# Skematik_Grader-GPS.net
KiCad netlist of a schematic drawn in Altium Designer
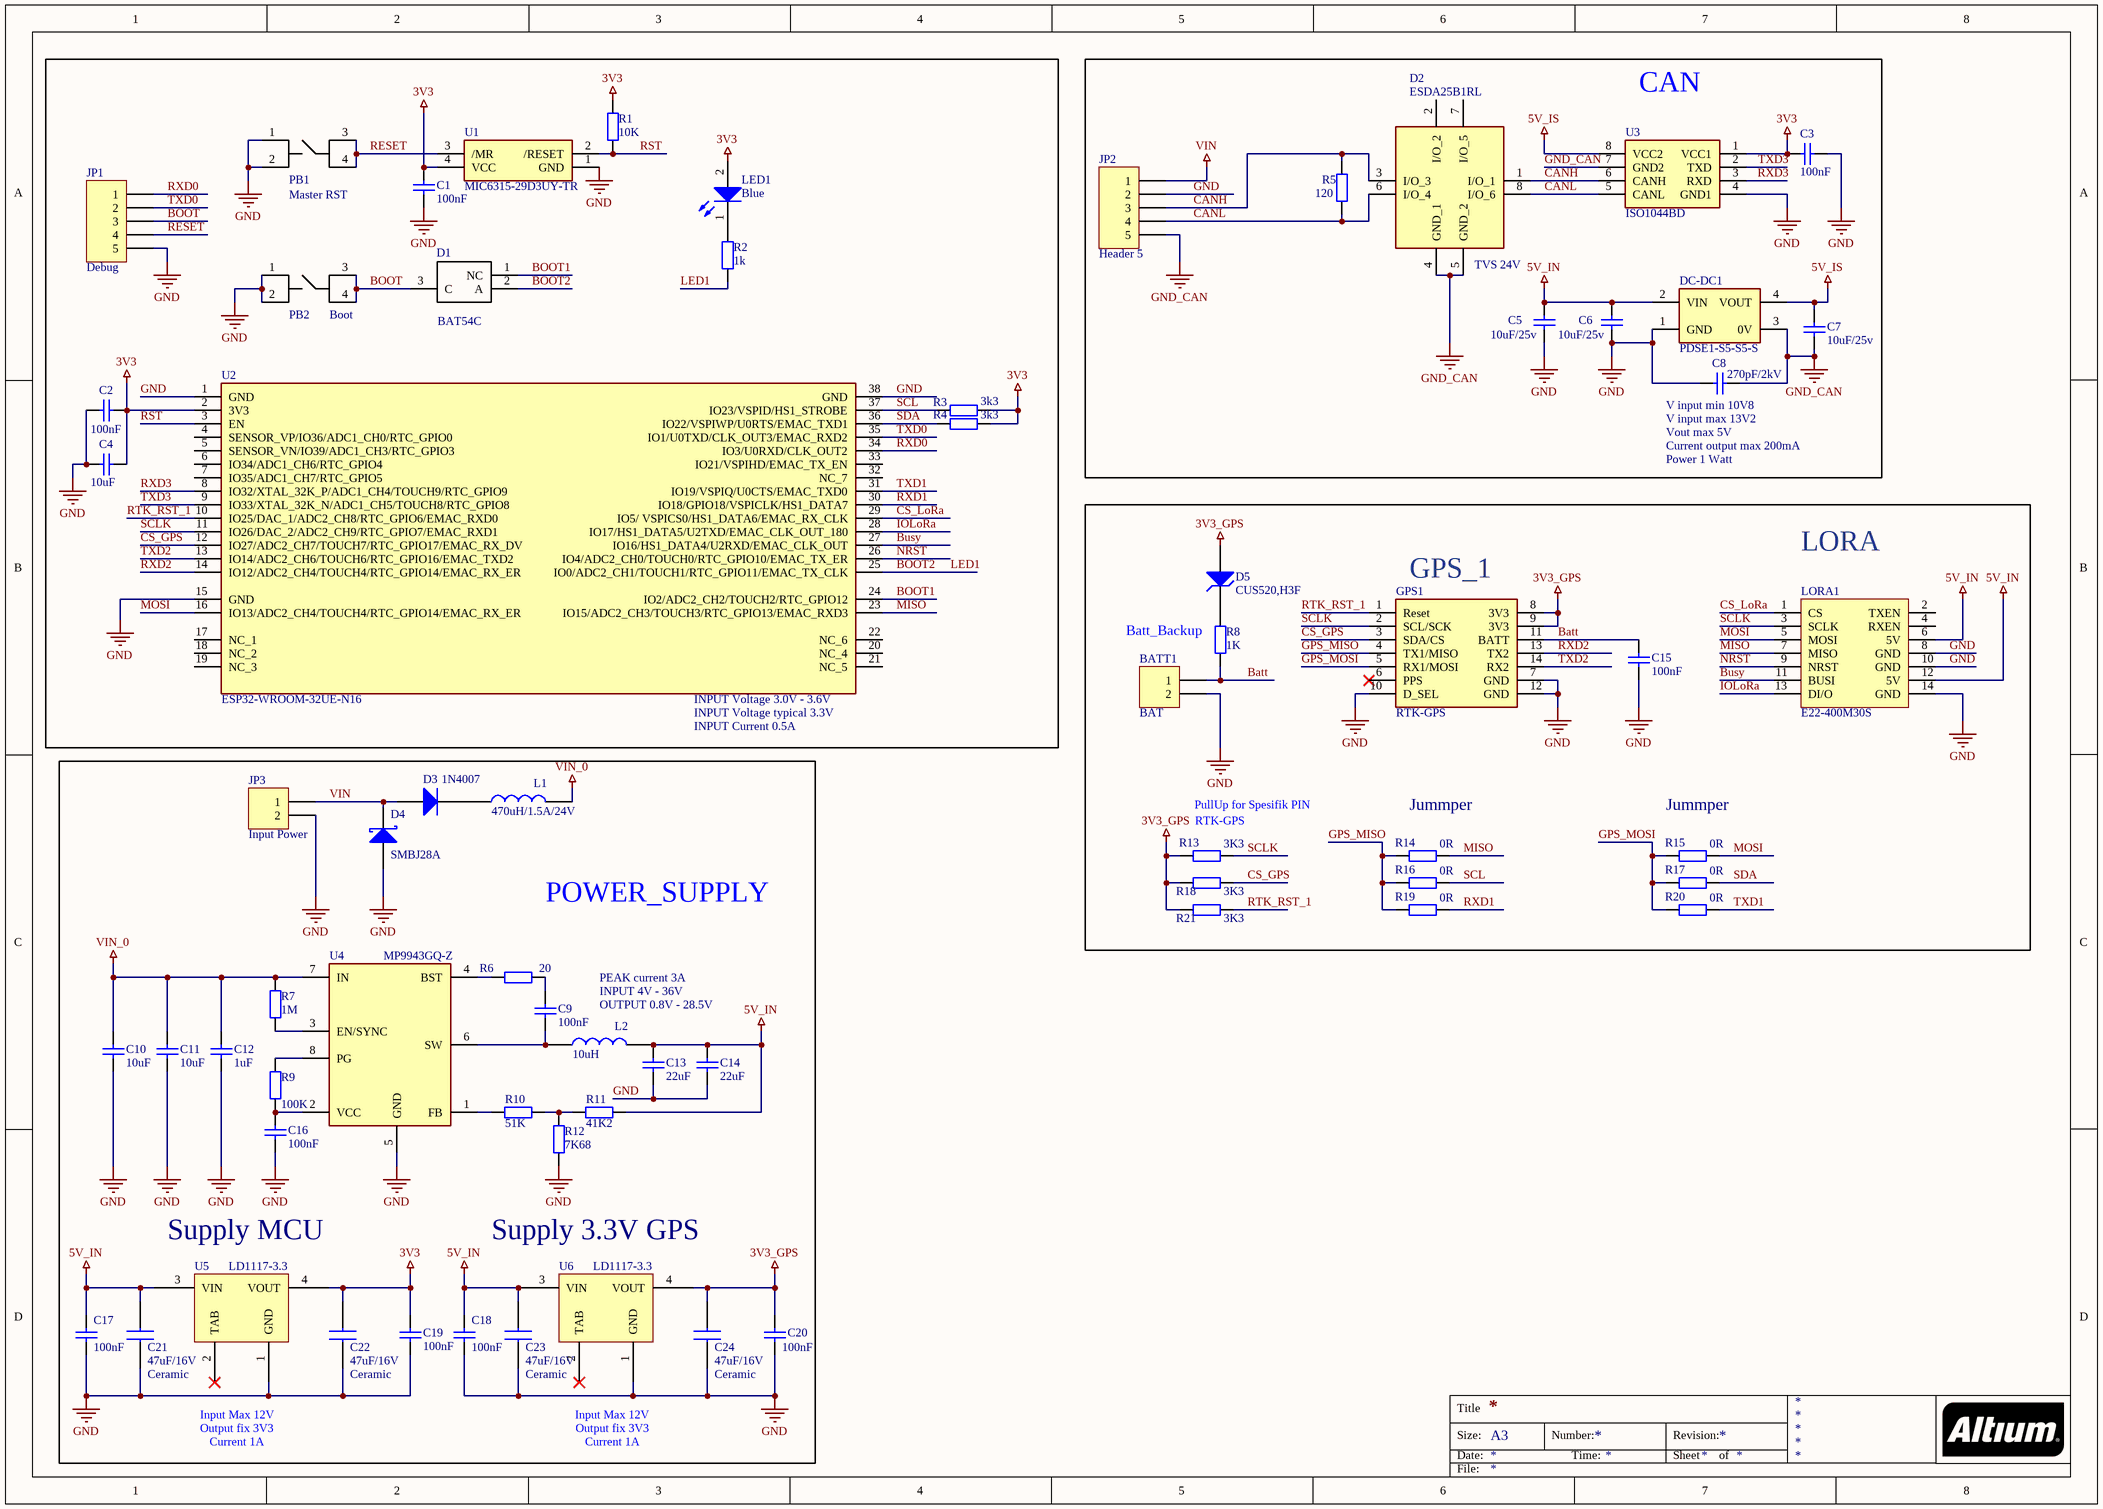
[diagram p0: Skematik_Grader-GPS.SchDoc]

(export (version "E")
  (design (tool "Eeschema 10.0.6"))
  (components
    (comp (ref "BATT1")
      (value "BAT")
      (footprint "CR1220")
      (description "Header, 2-Pin")
      (fields (field (name "PUBLISHER") "Altium Limited"))
      (libsource (lib "Miscellaneous Connectors") (part "MHDR1X2"))
    )
    (comp (ref "C1")
      (value "100nF")
      (footprint "CAPC2012X135N")
      (description "Capacitor")
      (fields (field (name "PUBLISHER") "Altium Limited"))
      (libsource (lib "Miscellaneous Devices") (part "Cap"))
    )
    (comp (ref "C2")
      (value "100nF")
      (footprint "CAPC2012X135N")
      (description "Capacitor")
      (fields (field (name "PUBLISHER") "Altium Limited"))
      (libsource (lib "Miscellaneous Devices") (part "Cap"))
    )
    (comp (ref "C3")
      (value "100nF")
      (footprint "CAPC2012X135N")
      (description "Capacitor")
      (fields (field (name "PUBLISHER") "Altium Limited"))
      (libsource (lib "Miscellaneous Devices") (part "Cap"))
    )
    (comp (ref "C4")
      (value "10uF")
      (footprint "CAPC3216X100N")
      (description "Capacitor")
      (fields (field (name "PUBLISHER") "Altium Limited"))
      (libsource (lib "Miscellaneous Devices") (part "Cap"))
    )
    (comp (ref "C5")
      (value "10uF/25v")
      (footprint "CAPC3216X180N")
      (description "Capacitor")
      (fields (field (name "Comment") "10uF") (field (name "PUBLISHER") "Altium Limited"))
      (libsource (lib "Miscellaneous Devices") (part "Cap"))
    )
    (comp (ref "C6")
      (value "10uF/25v")
      (footprint "CAPC3216X180N")
      (description "Capacitor")
      (fields (field (name "Comment") "10uF") (field (name "PUBLISHER") "Altium Limited"))
      (libsource (lib "Miscellaneous Devices") (part "Cap"))
    )
    (comp (ref "C7")
      (value "10uF/25v")
      (footprint "CAPC3216X100N")
      (description "Capacitor")
      (fields (field (name "Comment") "2.2uF/25V") (field (name "PUBLISHER") "Altium Limited"))
      (libsource (lib "Miscellaneous Devices") (part "Cap"))
    )
    (comp (ref "C8")
      (value "270pF/2kV")
      (footprint "CAPC3216X175N")
      (description "Capacitor")
      (fields (field (name "PUBLISHER") "Altium Limited"))
      (libsource (lib "Miscellaneous Devices") (part "Cap"))
    )
    (comp (ref "C9")
      (value "100nF")
      (footprint "CAPC2012X135N")
      (description "Capacitor")
      (fields (field (name "PUBLISHER") "Altium Limited"))
      (libsource (lib "Miscellaneous Devices") (part "Cap"))
    )
    (comp (ref "C10")
      (value "10uF")
      (footprint "CAPC3216X180N")
      (description "Capacitor")
      (fields (field (name "PUBLISHER") "Altium Limited"))
      (libsource (lib "Miscellaneous Devices") (part "Cap"))
    )
    (comp (ref "C11")
      (value "10uF")
      (footprint "CAPC3216X180N")
      (description "Capacitor")
      (fields (field (name "PUBLISHER") "Altium Limited"))
      (libsource (lib "Miscellaneous Devices") (part "Cap"))
    )
    (comp (ref "C12")
      (value "1uF")
      (footprint "CAPC2012X135N")
      (description "Capacitor")
      (fields (field (name "PUBLISHER") "Altium Limited"))
      (libsource (lib "Miscellaneous Devices") (part "Cap"))
    )
    (comp (ref "C13")
      (value "22uF")
      (footprint "CAPC3216X180N")
      (description "Capacitor")
      (fields (field (name "PUBLISHER") "Altium Limited"))
      (libsource (lib "Miscellaneous Devices") (part "Cap"))
    )
    (comp (ref "C14")
      (value "22uF")
      (footprint "CAPC3216X180N")
      (description "Capacitor")
      (fields (field (name "PUBLISHER") "Altium Limited"))
      (libsource (lib "Miscellaneous Devices") (part "Cap"))
    )
    (comp (ref "C15")
      (value "100nF")
      (footprint "CAPC2012X135N")
      (description "Capacitor")
      (fields (field (name "PUBLISHER") "Altium Limited"))
      (libsource (lib "Miscellaneous Devices") (part "Cap"))
    )
    (comp (ref "C16")
      (value "100nF")
      (footprint "CAPC2012X135N")
      (description "Capacitor")
      (fields (field (name "PUBLISHER") "Altium Limited"))
      (libsource (lib "Miscellaneous Devices") (part "Cap"))
    )
    (comp (ref "C17")
      (value "100nF")
      (footprint "CAPC2012X135N")
      (description "Capacitor")
      (fields (field (name "PUBLISHER") "Altium Limited"))
      (libsource (lib "Miscellaneous Devices") (part "Cap"))
    )
    (comp (ref "C18")
      (value "100nF")
      (footprint "CAPC2012X135N")
      (description "Capacitor")
      (fields (field (name "PUBLISHER") "Altium Limited"))
      (libsource (lib "Miscellaneous Devices") (part "Cap"))
    )
    (comp (ref "C19")
      (value "100nF")
      (footprint "CAPC2012X135N")
      (description "Capacitor")
      (fields (field (name "PUBLISHER") "Altium Limited"))
      (libsource (lib "Miscellaneous Devices") (part "Cap"))
    )
    (comp (ref "C20")
      (value "100nF")
      (footprint "CAPC2012X135N")
      (description "Capacitor")
      (fields (field (name "PUBLISHER") "Altium Limited"))
      (libsource (lib "Miscellaneous Devices") (part "Cap"))
    )
    (comp (ref "C21")
      (value "47uF/16V")
      (footprint "CAPC3225X220N")
      (description "Capacitor")
      (fields
        (field (name "MANUFACTURER_PART_NUMBER") "KCM55WC71E107MH13L")
        (field (name "MOUSER PART NUMBER") "81-KCM55WC71E107MH13")
        (field (name "TYPE") "Ceramic")
      )
      (libsource (lib "*") (part "KCM55WC71E107MH13L"))
    )
    (comp (ref "C22")
      (value "47uF/16V")
      (footprint "CAPC3225X220N")
      (description "Capacitor")
      (fields
        (field (name "MANUFACTURER_PART_NUMBER") "KCM55WC71E107MH13L")
        (field (name "MOUSER PART NUMBER") "81-KCM55WC71E107MH13")
        (field (name "TYPE") "Ceramic")
      )
      (libsource (lib "*") (part "KCM55WC71E107MH13L"))
    )
    (comp (ref "C23")
      (value "47uF/16V")
      (footprint "CAPC3225X220N")
      (description "Capacitor")
      (fields
        (field (name "MANUFACTURER_PART_NUMBER") "KCM55WC71E107MH13L")
        (field (name "MOUSER PART NUMBER") "81-KCM55WC71E107MH13")
        (field (name "TYPE") "Ceramic")
      )
      (libsource (lib "*") (part "KCM55WC71E107MH13L"))
    )
    (comp (ref "C24")
      (value "47uF/16V")
      (footprint "CAPC3225X220N")
      (description "Capacitor")
      (fields
        (field (name "MANUFACTURER_PART_NUMBER") "KCM55WC71E107MH13L")
        (field (name "MOUSER PART NUMBER") "81-KCM55WC71E107MH13")
        (field (name "TYPE") "Ceramic")
      )
      (libsource (lib "*") (part "KCM55WC71E107MH13L"))
    )
    (comp (ref "D1") (value "BAT54C") (footprint "SC59-3") (libsource (lib "Sigit") (part "RB420")))
    (comp (ref "D2")
      (value "ESDA25B1RL")
      (footprint "SOIC127P600X175-8AN")
      (description "TVS DIODA")
      (fields (field (name "MOUSER PART NUMBER") "511-ESDA25B1-TR"))
      (libsource (lib "bayu") (part "ESDA25B1RL"))
    )
    (comp (ref "D3")
      (value "1N4007")
      (footprint "DO-214AC")
      (description "1 Amp General Purpose Rectifier")
      (fields (field (name "PUBLISHER") "Altium Limited"))
      (libsource (lib "Miscellaneous Devices") (part "Diode 1N4001"))
    )
    (comp (ref "D4")
      (value "SMBJ28A")
      (footprint "PBL - SMD Packages:DO-214AA")
      (description "Schottky Diode")
      (fields (field (name "PUBLISHER") "Altium Limited"))
      (libsource (lib "Miscellaneous Devices") (part "D Schottky"))
    )
    (comp (ref "D5")
      (value "CUS520,H3F")
      (footprint "SOD323")
      (description "Zener Diode")
      (fields (field (name "PUBLISHER") "Altium Limited"))
      (libsource (lib "Miscellaneous Devices") (part "D Zener"))
    )
    (comp (ref "DC-DC1")
      (value "PDSE1-S5-S5-S")
      (footprint "PDSE1-S (1W)")
      (description "DC-DC 24 to 12 \r\nPDSE1-S24-S12-S")
      (libsource (lib "rapp") (part "PDSE1-S24-S12-S"))
    )
    (comp (ref "GPS1")
      (value "RTK-GPS")
      (footprint "ZED-F9P")
      (description "GPS Sensor")
      (libsource (lib "rapp") (part "ZED-F9P"))
    )
    (comp (ref "JP1")
      (value "Debug")
      (footprint "HDR1X5")
      (description "Header, 5-Pin")
      (fields (field (name "PUBLISHER") "Altium Limited"))
      (libsource (lib "Miscellaneous Connectors") (part "Header 5"))
    )
    (comp (ref "JP2")
      (value "Header 5")
      (footprint "Term_Block - 5P")
      (description "Header, 5-Pin")
      (fields (field (name "PUBLISHER") "Altium Limited"))
      (libsource (lib "Miscellaneous Connectors") (part "Header 5"))
    )
    (comp (ref "JP3")
      (value "Input Power")
      (footprint "2828362")
      (description "Header, 2-Pin")
      (fields (field (name "PUBLISHER") "Altium Limited"))
      (libsource (lib "Miscellaneous Connectors") (part "Header 2"))
    )
    (comp (ref "L1")
      (value "470uH/1.5A/24V")
      (footprint "INDP9630X28N")
      (description "Inductor")
      (fields
        (field (name "MANUFACTURER_PART_NUMBER") "MPL-AL5050-100")
        (field (name "MOUSER PART NUMBER") "946-MPL-AL5050-100")
      )
      (libsource (lib "*") (part "MPL-AL5050-100"))
    )
    (comp (ref "L2")
      (value "10uH")
      (footprint "IND_5.4x5.3")
      (description "Inductor")
      (fields
        (field (name "MANUFACTURER_PART_NUMBER") "MPL-AL5050-100")
        (field (name "MOUSER PART NUMBER") "946-MPL-AL5050-100")
      )
      (libsource (lib "*") (part "MPL-AL5050-100"))
    )
    (comp (ref "LED1")
      (value "Blue")
      (footprint "LED-0805-A")
      (description "Typical Blue GaAs LED")
      (fields (field (name "PUBLISHER") "Altium Limited"))
      (libsource (lib "Miscellaneous Devices") (part "LED1"))
    )
    (comp (ref "LORA1")
      (value "E22-400M30S")
      (footprint "22s-V3")
      (description "Lora 22S / Lora 30S")
      (libsource (lib "rapp") (part "Lora"))
    )
    (comp (ref "PB1")
      (value "Master RST")
      (footprint "PushButton1688")
      (libsource (lib "Sigit") (part "PB_SW_1"))
    )
    (comp (ref "PB2") (value "Boot") (footprint "PushButton1688") (libsource (lib "Sigit") (part "PB_SW_1")))
    (comp (ref "R1")
      (value "10K")
      (footprint "RESC2012X70N")
      (description "Resistor")
      (fields (field (name "PUBLISHER") "Altium Limited"))
      (libsource (lib "Miscellaneous Devices") (part "Res2"))
    )
    (comp (ref "R2")
      (value "1k")
      (footprint "RESC2012X70N")
      (description "Resistor")
      (fields (field (name "PUBLISHER") "Altium Limited"))
      (libsource (lib "Miscellaneous Devices") (part "Res2"))
    )
    (comp (ref "R3")
      (value "3k3")
      (footprint "RESC2012X70N")
      (description "Resistor")
      (fields (field (name "PUBLISHER") "Altium Limited"))
      (libsource (lib "Miscellaneous Devices") (part "Res2"))
    )
    (comp (ref "R4")
      (value "3k3")
      (footprint "RESC2012X70N")
      (description "Resistor")
      (fields (field (name "PUBLISHER") "Altium Limited"))
      (libsource (lib "Miscellaneous Devices") (part "Res2"))
    )
    (comp (ref "R5")
      (value "120")
      (footprint "RESC2012X70N")
      (description "Resistor")
      (fields (field (name "PUBLISHER") "Altium Limited"))
      (libsource (lib "") (part "Res2_3"))
    )
    (comp (ref "R6")
      (value "20")
      (footprint "RESC2012X70N")
      (description "Resistor")
      (fields (field (name "PUBLISHER") "Altium Limited"))
      (libsource (lib "") (part "Res2_3"))
    )
    (comp (ref "R7")
      (value "1M")
      (footprint "RESC2012X70N")
      (description "Resistor")
      (fields (field (name "PUBLISHER") "Altium Limited"))
      (libsource (lib "") (part "Res2_1"))
    )
    (comp (ref "R8")
      (value "1K")
      (footprint "RESC2012X70N")
      (description "Resistor")
      (fields (field (name "PUBLISHER") "Altium Limited"))
      (libsource (lib "") (part "Res2_2"))
    )
    (comp (ref "R9")
      (value "100K")
      (footprint "RESC2012X70N")
      (description "Resistor")
      (fields (field (name "PUBLISHER") "Altium Limited"))
      (libsource (lib "") (part "Res2_1"))
    )
    (comp (ref "R10")
      (value "51K")
      (footprint "RESC2012X70N")
      (description "Resistor")
      (fields (field (name "PUBLISHER") "Altium Limited"))
      (libsource (lib "") (part "Res2_3"))
    )
    (comp (ref "R11")
      (value "41K2")
      (footprint "RESC2012X70N")
      (description "Resistor")
      (fields (field (name "PUBLISHER") "Altium Limited"))
      (libsource (lib "") (part "Res2_3"))
    )
    (comp (ref "R12")
      (value "7K68")
      (footprint "RESC2012X70N")
      (description "Resistor")
      (fields (field (name "PUBLISHER") "Altium Limited"))
      (libsource (lib "Miscellaneous Devices") (part "Res2"))
    )
    (comp (ref "R13")
      (value "3K3")
      (footprint "RESC2012X70N")
      (description "Resistor")
      (fields (field (name "PUBLISHER") "Altium Limited"))
      (libsource (lib "") (part "Res2_1"))
    )
    (comp (ref "R14")
      (value "0R")
      (footprint "RESC2012X70N")
      (description "Resistor")
      (fields (field (name "PUBLISHER") "Altium Limited"))
      (libsource (lib "") (part "Res2_1"))
    )
    (comp (ref "R15")
      (value "0R")
      (footprint "RESC2012X70N")
      (description "Resistor")
      (fields (field (name "PUBLISHER") "Altium Limited"))
      (libsource (lib "") (part "Res2_1"))
    )
    (comp (ref "R16")
      (value "0R")
      (footprint "RESC2012X70N")
      (description "Resistor")
      (fields (field (name "PUBLISHER") "Altium Limited"))
      (libsource (lib "") (part "Res2_1"))
    )
    (comp (ref "R17")
      (value "0R")
      (footprint "RESC2012X70N")
      (description "Resistor")
      (fields (field (name "PUBLISHER") "Altium Limited"))
      (libsource (lib "") (part "Res2_1"))
    )
    (comp (ref "R18")
      (value "3K3")
      (footprint "RESC2012X70N")
      (description "Resistor")
      (fields (field (name "PUBLISHER") "Altium Limited"))
      (libsource (lib "Miscellaneous Devices") (part "Res2"))
    )
    (comp (ref "R19")
      (value "0R")
      (footprint "RESC2012X70N")
      (description "Resistor")
      (fields (field (name "PUBLISHER") "Altium Limited"))
      (libsource (lib "") (part "Res2_1"))
    )
    (comp (ref "R20")
      (value "0R")
      (footprint "RESC2012X70N")
      (description "Resistor")
      (fields (field (name "PUBLISHER") "Altium Limited"))
      (libsource (lib "") (part "Res2_1"))
    )
    (comp (ref "R21")
      (value "3K3")
      (footprint "RESC2012X70N")
      (description "Resistor")
      (fields (field (name "PUBLISHER") "Altium Limited"))
      (libsource (lib "Miscellaneous Devices") (part "Res2"))
    )
    (comp (ref "U1")
      (value "MIC6315-29D3UY-TR")
      (footprint "MIC631529D3UYTR")
      (description "Integrated Circuit")
      (fields (field (name "MOUSER PART NUMBER") "998-MIC6315-29D3UYTR"))
      (libsource (lib "*") (part "MIC6315-29D3UY-TR"))
    )
    (comp (ref "U2")
      (value "ESP32-WROOM-32UE-N16")
      (footprint "ESP32WROOM32UEN16")
      (libsource (lib "rapp") (part "ESP32-WROOM-32UE-N16A"))
    )
    (comp (ref "U3")
      (value "ISO1044BD")
      (footprint "SOIC127P600X175-8AN")
      (description "Integrated Circuit")
      (fields (field (name "MOUSER PART NUMBER") "595-ISO1044BD"))
      (libsource (lib "*") (part "ISO1044BD"))
    )
    (comp (ref "U4")
      (value "MP9943GQ-Z")
      (footprint "MP9943GQz-smd")
      (description "Integrated Circuit")
      (fields (field (name "MOUSER PART NUMBER") "946-MP9943GQ-Z"))
      (libsource (lib "bayu") (part "MP9943GQ-Z"))
    )
    (comp (ref "U5")
      (value "LD1117-3.3")
      (footprint "PBL - SMD Packages:TO-252")
      (description "AP2114D-3.3TRG1, 3.3V LDO Voltage Regulator")
      (libsource (lib "Sigit") (part "LM1117-3.3V"))
    )
    (comp (ref "U6")
      (value "LD1117-3.3")
      (footprint "PBL - SMD Packages:TO-252")
      (description "AP2114D-3.3TRG1, 3.3V LDO Voltage Regulator")
      (libsource (lib "Sigit") (part "LM1117-3.3V"))
    )
  )
  (nets
    (net (code "1") (name "/BOOT") (class "Default")
      (node (ref "D1") (pin "3") (pinfunction "C_3") (pintype "passive"))
      (node (ref "JP1") (pin "3") (pinfunction "3_3") (pintype "passive"))
      (node (ref "PB2") (pin "3") (pinfunction "3_3") (pintype "passive"))
      (node (ref "PB2") (pin "4") (pinfunction "4_4") (pintype "passive"))
    )
    (net (code "2") (name "/BOOT1") (class "Default")
      (node (ref "D1") (pin "1") (pinfunction "NC_1") (pintype "passive"))
      (node (ref "U2") (pin "24") (pinfunction "IO2/ADC2_CH2/TOUCH2/RTC_GPIO12_24") (pintype "passive"))
    )
    (net (code "3") (name "/BOOT2") (class "Default")
      (node (ref "D1") (pin "2") (pinfunction "A_2") (pintype "passive"))
      (node (ref "R2") (pin "2") (pinfunction "2_2") (pintype "passive"))
      (node (ref "U2") (pin "25") (pinfunction "IO0/ADC2_CH1/TOUCH1/RTC_GPIO11/EMAC_TX_CLK_25") (pintype "passive"))
    )
    (net (code "4") (name "/Batt") (class "Default")
      (node (ref "BATT1") (pin "1") (pinfunction "1_1") (pintype "passive"))
      (node (ref "C15") (pin "2") (pinfunction "2_2") (pintype "passive"))
      (node (ref "GPS1") (pin "11") (pinfunction "BATT_11") (pintype "passive"))
      (node (ref "R8") (pin "1") (pinfunction "1_1") (pintype "passive"))
    )
    (net (code "5") (name "/Busy") (class "Default")
      (node (ref "LORA1") (pin "11") (pinfunction "BUSI_11") (pintype "passive"))
      (node (ref "U2") (pin "27") (pinfunction "IO16/HS1_DATA4/U2RXD/EMAC_CLK_OUT_27") (pintype "passive"))
    )
    (net (code "6") (name "/CANH") (class "Default")
      (node (ref "D2") (pin "1") (pinfunction "I/O_1_1") (pintype "passive"))
      (node (ref "D2") (pin "3") (pinfunction "I/O_3_3") (pintype "passive"))
      (node (ref "JP2") (pin "3") (pinfunction "3_3") (pintype "passive"))
      (node (ref "R5") (pin "1") (pinfunction "1_1") (pintype "passive"))
      (node (ref "U3") (pin "6") (pinfunction "CANH_6") (pintype "passive"))
    )
    (net (code "7") (name "/CANL") (class "Default")
      (node (ref "D2") (pin "6") (pinfunction "I/O_4_6") (pintype "passive"))
      (node (ref "D2") (pin "8") (pinfunction "I/O_6_8") (pintype "passive"))
      (node (ref "JP2") (pin "4") (pinfunction "4_4") (pintype "passive"))
      (node (ref "R5") (pin "2") (pinfunction "2_2") (pintype "passive"))
      (node (ref "U3") (pin "5") (pinfunction "CANL_5") (pintype "passive"))
    )
    (net (code "8") (name "/CS_GPS") (class "Default")
      (node (ref "GPS1") (pin "3") (pinfunction "SDA/CS_3") (pintype "passive"))
      (node (ref "R18") (pin "1") (pinfunction "1_1") (pintype "passive"))
      (node (ref "U2") (pin "12") (pinfunction "IO27/ADC2_CH7/TOUCH7/RTC_GPIO17/EMAC_RX_DV_12") (pintype "passive"))
    )
    (net (code "9") (name "/CS_LoRa") (class "Default")
      (node (ref "LORA1") (pin "1") (pinfunction "CS_1") (pintype "passive"))
      (node (ref "U2") (pin "29") (pinfunction "IO5/_VSPICS0/HS1_DATA6/EMAC_RX_CLK_29") (pintype "passive"))
    )
    (net (code "10") (name "/GPS_MISO") (class "Default")
      (node (ref "GPS1") (pin "4") (pinfunction "TX1/MISO_4") (pintype "passive"))
      (node (ref "R14") (pin "1") (pinfunction "1_1") (pintype "passive"))
      (node (ref "R16") (pin "1") (pinfunction "1_1") (pintype "passive"))
      (node (ref "R19") (pin "1") (pinfunction "1_1") (pintype "passive"))
    )
    (net (code "11") (name "/GPS_MOSI") (class "Default")
      (node (ref "GPS1") (pin "5") (pinfunction "RX1/MOSI_5") (pintype "passive"))
      (node (ref "R15") (pin "1") (pinfunction "1_1") (pintype "passive"))
      (node (ref "R17") (pin "1") (pinfunction "1_1") (pintype "passive"))
      (node (ref "R20") (pin "1") (pinfunction "1_1") (pintype "passive"))
    )
    (net (code "12") (name "/IOLoRa") (class "Default")
      (node (ref "LORA1") (pin "13") (pinfunction "DI/O_13") (pintype "passive"))
      (node (ref "U2") (pin "28") (pinfunction "IO17/HS1_DATA5/U2TXD/EMAC_CLK_OUT_180_28") (pintype "passive"))
    )
    (net (code "13") (name "/MISO") (class "Default")
      (node (ref "LORA1") (pin "7") (pinfunction "MISO_7") (pintype "passive"))
      (node (ref "R14") (pin "2") (pinfunction "2_2") (pintype "passive"))
      (node (ref "U2") (pin "23") (pinfunction "IO15/ADC2_CH3/TOUCH3/RTC_GPIO13/EMAC_RXD3_23") (pintype "passive"))
    )
    (net (code "14") (name "/MOSI") (class "Default")
      (node (ref "LORA1") (pin "5") (pinfunction "MOSI_5") (pintype "passive"))
      (node (ref "R15") (pin "2") (pinfunction "2_2") (pintype "passive"))
      (node (ref "U2") (pin "16") (pinfunction "IO13/ADC2_CH4/TOUCH4/RTC_GPIO14/EMAC_RX_ER_16") (pintype "passive"))
    )
    (net (code "15") (name "/NRST") (class "Default")
      (node (ref "LORA1") (pin "9") (pinfunction "NRST_9") (pintype "passive"))
      (node (ref "U2") (pin "26") (pinfunction "IO4/ADC2_CH0/TOUCH0/RTC_GPIO10/EMAC_TX_ER_26") (pintype "passive"))
    )
    (net (code "16") (name "/RESET") (class "Default")
      (node (ref "JP1") (pin "4") (pinfunction "4_4") (pintype "passive"))
      (node (ref "PB1") (pin "3") (pinfunction "3_3") (pintype "passive"))
      (node (ref "PB1") (pin "4") (pinfunction "4_4") (pintype "passive"))
      (node (ref "U1") (pin "3") (pinfunction "/MR_3") (pintype "passive"))
    )
    (net (code "17") (name "/RST") (class "Default")
      (node (ref "R1") (pin "2") (pinfunction "2_2") (pintype "passive"))
      (node (ref "U1") (pin "2") (pinfunction "/RESET_2") (pintype "passive"))
      (node (ref "U2") (pin "3") (pinfunction "EN_3") (pintype "passive"))
    )
    (net (code "18") (name "/RTK_RST_1") (class "Default")
      (node (ref "GPS1") (pin "1") (pinfunction "Reset_1") (pintype "passive"))
      (node (ref "R21") (pin "1") (pinfunction "1_1") (pintype "passive"))
      (node (ref "U2") (pin "10") (pinfunction "IO25/DAC_1/ADC2_CH8/RTC_GPIO6/EMAC_RXD0_10") (pintype "passive"))
    )
    (net (code "19") (name "/RXD0") (class "Default")
      (node (ref "JP1") (pin "1") (pinfunction "1_1") (pintype "passive"))
      (node (ref "U2") (pin "34") (pinfunction "IO3/U0RXD/CLK_OUT2_34") (pintype "passive"))
    )
    (net (code "20") (name "/RXD1") (class "Default")
      (node (ref "R19") (pin "2") (pinfunction "2_2") (pintype "passive"))
      (node (ref "U2") (pin "30") (pinfunction "IO18/GPIO18/VSPICLK/HS1_DATA7_30") (pintype "passive"))
    )
    (net (code "21") (name "/RXD2") (class "Default")
      (node (ref "GPS1") (pin "13") (pinfunction "TX2_13") (pintype "passive"))
      (node (ref "U2") (pin "14") (pinfunction "IO12/ADC2_CH4/TOUCH4/RTC_GPIO14/EMAC_RX_ER_14") (pintype "passive"))
    )
    (net (code "22") (name "/RXD3") (class "Default")
      (node (ref "U2") (pin "8") (pinfunction "IO32/XTAL_32K_P/ADC1_CH4/TOUCH9/RTC_GPIO9_8") (pintype "passive"))
      (node (ref "U3") (pin "3") (pinfunction "RXD_3") (pintype "passive"))
    )
    (net (code "23") (name "/SCL") (class "Default")
      (node (ref "R16") (pin "2") (pinfunction "2_2") (pintype "passive"))
      (node (ref "R3") (pin "2") (pinfunction "2_2") (pintype "passive"))
      (node (ref "U2") (pin "37") (pinfunction "IO23/VSPID/HS1_STROBE_37") (pintype "passive"))
    )
    (net (code "24") (name "/SCLK") (class "Default")
      (node (ref "GPS1") (pin "2") (pinfunction "SCL/SCK_2") (pintype "passive"))
      (node (ref "LORA1") (pin "3") (pinfunction "SCLK_3") (pintype "passive"))
      (node (ref "R13") (pin "2") (pinfunction "2_2") (pintype "passive"))
      (node (ref "U2") (pin "11") (pinfunction "IO26/DAC_2/ADC2_CH9/RTC_GPIO7/EMAC_RXD1_11") (pintype "passive"))
    )
    (net (code "25") (name "/SDA") (class "Default")
      (node (ref "R17") (pin "2") (pinfunction "2_2") (pintype "passive"))
      (node (ref "R4") (pin "2") (pinfunction "2_2") (pintype "passive"))
      (node (ref "U2") (pin "36") (pinfunction "IO22/VSPIWP/U0RTS/EMAC_TXD1_36") (pintype "passive"))
    )
    (net (code "26") (name "/TXD0") (class "Default")
      (node (ref "JP1") (pin "2") (pinfunction "2_2") (pintype "passive"))
      (node (ref "U2") (pin "35") (pinfunction "IO1/U0TXD/CLK_OUT3/EMAC_RXD2_35") (pintype "passive"))
    )
    (net (code "27") (name "/TXD1") (class "Default")
      (node (ref "R20") (pin "2") (pinfunction "2_2") (pintype "passive"))
      (node (ref "U2") (pin "31") (pinfunction "IO19/VSPIQ/U0CTS/EMAC_TXD0_31") (pintype "passive"))
    )
    (net (code "28") (name "/TXD2") (class "Default")
      (node (ref "GPS1") (pin "14") (pinfunction "RX2_14") (pintype "passive"))
      (node (ref "U2") (pin "13") (pinfunction "IO14/ADC2_CH6/TOUCH6/RTC_GPIO16/EMAC_TXD2_13") (pintype "passive"))
    )
    (net (code "29") (name "/TXD3") (class "Default")
      (node (ref "U2") (pin "9") (pinfunction "IO33/XTAL_32K_N/ADC1_CH5/TOUCH8/RTC_GPIO8_9") (pintype "passive"))
      (node (ref "U3") (pin "2") (pinfunction "TXD_2") (pintype "passive"))
    )
    (net (code "30") (name "3V3") (class "Default")
      (node (ref "C1") (pin "1") (pinfunction "1_1") (pintype "passive"))
      (node (ref "C19") (pin "2") (pinfunction "2_2") (pintype "passive"))
      (node (ref "C2") (pin "2") (pinfunction "2_2") (pintype "passive"))
      (node (ref "C22") (pin "1") (pinfunction "1_1") (pintype "passive"))
      (node (ref "C3") (pin "1") (pinfunction "1_1") (pintype "passive"))
      (node (ref "C4") (pin "2") (pinfunction "2_2") (pintype "passive"))
      (node (ref "LED1") (pin "2") (pinfunction "A_2") (pintype "passive"))
      (node (ref "R1") (pin "1") (pinfunction "1_1") (pintype "passive"))
      (node (ref "R3") (pin "1") (pinfunction "1_1") (pintype "passive"))
      (node (ref "R4") (pin "1") (pinfunction "1_1") (pintype "passive"))
      (node (ref "U1") (pin "4") (pinfunction "VCC_4") (pintype "passive"))
      (node (ref "U2") (pin "2") (pinfunction "3V3_2") (pintype "passive"))
      (node (ref "U3") (pin "1") (pinfunction "VCC1_1") (pintype "passive"))
      (node (ref "U5") (pin "4") (pinfunction "VOUT_4") (pintype "passive"))
    )
    (net (code "31") (name "3V3_GPS") (class "Default")
      (node (ref "C20") (pin "2") (pinfunction "2_2") (pintype "passive"))
      (node (ref "C24") (pin "1") (pinfunction "1_1") (pintype "passive"))
      (node (ref "D5") (pin "1") (pinfunction "A_1") (pintype "passive"))
      (node (ref "GPS1") (pin "8") (pinfunction "3V3_8") (pintype "passive"))
      (node (ref "GPS1") (pin "9") (pinfunction "3V3_9") (pintype "passive"))
      (node (ref "R13") (pin "1") (pinfunction "1_1") (pintype "passive"))
      (node (ref "R18") (pin "2") (pinfunction "2_2") (pintype "passive"))
      (node (ref "R21") (pin "2") (pinfunction "2_2") (pintype "passive"))
      (node (ref "U6") (pin "4") (pinfunction "VOUT_4") (pintype "passive"))
    )
    (net (code "32") (name "5V_IN") (class "Default")
      (node (ref "C13") (pin "2") (pinfunction "2_2") (pintype "passive"))
      (node (ref "C14") (pin "2") (pinfunction "2_2") (pintype "passive"))
      (node (ref "C17") (pin "2") (pinfunction "2_2") (pintype "passive"))
      (node (ref "C18") (pin "2") (pinfunction "2_2") (pintype "passive"))
      (node (ref "C21") (pin "1") (pinfunction "1_1") (pintype "passive"))
      (node (ref "C23") (pin "1") (pinfunction "1_1") (pintype "passive"))
      (node (ref "C5") (pin "2") (pinfunction "2_2") (pintype "passive"))
      (node (ref "C6") (pin "2") (pinfunction "2_2") (pintype "passive"))
      (node (ref "DC-DC1") (pin "2") (pinfunction "VIN_2") (pintype "passive"))
      (node (ref "L2") (pin "2") (pinfunction "2_2") (pintype "passive"))
      (node (ref "LORA1") (pin "12") (pinfunction "5V_12") (pintype "passive"))
      (node (ref "LORA1") (pin "6") (pinfunction "5V_6") (pintype "passive"))
      (node (ref "R11") (pin "1") (pinfunction "1_1") (pintype "passive"))
      (node (ref "U5") (pin "3") (pinfunction "VIN_3") (pintype "passive"))
      (node (ref "U6") (pin "3") (pinfunction "VIN_3") (pintype "passive"))
    )
    (net (code "33") (name "5V_IS") (class "Default")
      (node (ref "C7") (pin "1") (pinfunction "1_1") (pintype "passive"))
      (node (ref "DC-DC1") (pin "4") (pinfunction "VOUT_4") (pintype "passive"))
      (node (ref "U3") (pin "8") (pinfunction "VCC2_8") (pintype "passive"))
    )
    (net (code "34") (name "GND") (class "Default")
      (node (ref "BATT1") (pin "2") (pinfunction "2_2") (pintype "passive"))
      (node (ref "C1") (pin "2") (pinfunction "2_2") (pintype "passive"))
      (node (ref "C10") (pin "1") (pinfunction "1_1") (pintype "passive"))
      (node (ref "C11") (pin "1") (pinfunction "1_1") (pintype "passive"))
      (node (ref "C12") (pin "1") (pinfunction "1_1") (pintype "passive"))
      (node (ref "C13") (pin "1") (pinfunction "1_1") (pintype "passive"))
      (node (ref "C14") (pin "1") (pinfunction "1_1") (pintype "passive"))
      (node (ref "C15") (pin "1") (pinfunction "1_1") (pintype "passive"))
      (node (ref "C16") (pin "1") (pinfunction "1_1") (pintype "passive"))
      (node (ref "C17") (pin "1") (pinfunction "1_1") (pintype "passive"))
      (node (ref "C18") (pin "1") (pinfunction "1_1") (pintype "passive"))
      (node (ref "C19") (pin "1") (pinfunction "1_1") (pintype "passive"))
      (node (ref "C2") (pin "1") (pinfunction "1_1") (pintype "passive"))
      (node (ref "C20") (pin "1") (pinfunction "1_1") (pintype "passive"))
      (node (ref "C21") (pin "2") (pinfunction "2_2") (pintype "passive"))
      (node (ref "C22") (pin "2") (pinfunction "2_2") (pintype "passive"))
      (node (ref "C23") (pin "2") (pinfunction "2_2") (pintype "passive"))
      (node (ref "C24") (pin "2") (pinfunction "2_2") (pintype "passive"))
      (node (ref "C3") (pin "2") (pinfunction "2_2") (pintype "passive"))
      (node (ref "C4") (pin "1") (pinfunction "1_1") (pintype "passive"))
      (node (ref "C5") (pin "1") (pinfunction "1_1") (pintype "passive"))
      (node (ref "C6") (pin "1") (pinfunction "1_1") (pintype "passive"))
      (node (ref "C8") (pin "1") (pinfunction "1_1") (pintype "passive"))
      (node (ref "D4") (pin "1") (pinfunction "A_1") (pintype "passive"))
      (node (ref "DC-DC1") (pin "1") (pinfunction "GND_1") (pintype "passive"))
      (node (ref "GPS1") (pin "10") (pinfunction "D_SEL_10") (pintype "passive"))
      (node (ref "GPS1") (pin "12") (pinfunction "GND_12") (pintype "passive"))
      (node (ref "GPS1") (pin "7") (pinfunction "GND_7") (pintype "passive"))
      (node (ref "JP1") (pin "5") (pinfunction "5_5") (pintype "passive"))
      (node (ref "JP2") (pin "2") (pinfunction "2_2") (pintype "passive"))
      (node (ref "JP3") (pin "2") (pinfunction "2_2") (pintype "passive"))
      (node (ref "LORA1") (pin "10") (pinfunction "GND_10") (pintype "passive"))
      (node (ref "LORA1") (pin "14") (pinfunction "GND_14") (pintype "passive"))
      (node (ref "LORA1") (pin "8") (pinfunction "GND_8") (pintype "passive"))
      (node (ref "PB1") (pin "1") (pinfunction "1_1") (pintype "passive"))
      (node (ref "PB1") (pin "2") (pinfunction "2_2") (pintype "passive"))
      (node (ref "PB2") (pin "1") (pinfunction "1_1") (pintype "passive"))
      (node (ref "PB2") (pin "2") (pinfunction "2_2") (pintype "passive"))
      (node (ref "R12") (pin "2") (pinfunction "2_2") (pintype "passive"))
      (node (ref "U1") (pin "1") (pinfunction "GND_1") (pintype "passive"))
      (node (ref "U2") (pin "1") (pinfunction "GND_1") (pintype "passive"))
      (node (ref "U2") (pin "15") (pinfunction "GND_15") (pintype "passive"))
      (node (ref "U2") (pin "38") (pinfunction "GND_38") (pintype "passive"))
      (node (ref "U3") (pin "4") (pinfunction "GND1_4") (pintype "passive"))
      (node (ref "U4") (pin "5") (pinfunction "GND_5") (pintype "passive"))
      (node (ref "U5") (pin "1") (pinfunction "GND_1") (pintype "passive"))
      (node (ref "U6") (pin "1") (pinfunction "GND_1") (pintype "passive"))
    )
    (net (code "35") (name "GND_CAN") (class "Default")
      (node (ref "C7") (pin "2") (pinfunction "2_2") (pintype "passive"))
      (node (ref "C8") (pin "2") (pinfunction "2_2") (pintype "passive"))
      (node (ref "D2") (pin "4") (pinfunction "GND_1_4") (pintype "passive"))
      (node (ref "D2") (pin "5") (pinfunction "GND_2_5") (pintype "passive"))
      (node (ref "DC-DC1") (pin "3") (pinfunction "0V_3") (pintype "passive"))
      (node (ref "JP2") (pin "5") (pinfunction "5_5") (pintype "passive"))
      (node (ref "U3") (pin "7") (pinfunction "GND2_7") (pintype "passive"))
    )
    (net (code "36") (name "Net-(C9-Pad2)") (class "Default")
      (node (ref "C9") (pin "2") (pinfunction "2_2") (pintype "passive"))
      (node (ref "R6") (pin "1") (pinfunction "1_1") (pintype "passive"))
    )
    (net (code "37") (name "Net-(D3-K)") (class "Default")
      (node (ref "D3") (pin "2") (pinfunction "K_2") (pintype "passive"))
      (node (ref "L1") (pin "1") (pinfunction "1_1") (pintype "passive"))
    )
    (net (code "38") (name "Net-(D5-K)") (class "Default")
      (node (ref "D5") (pin "2") (pinfunction "K_2") (pintype "passive"))
      (node (ref "R8") (pin "2") (pinfunction "2_2") (pintype "passive"))
    )
    (net (code "39") (name "Net-(LED1-K)") (class "Default")
      (node (ref "LED1") (pin "1") (pinfunction "K_1") (pintype "passive"))
      (node (ref "R2") (pin "1") (pinfunction "1_1") (pintype "passive"))
    )
    (net (code "40") (name "Net-(R10-Pad1)") (class "Default")
      (node (ref "R10") (pin "1") (pinfunction "1_1") (pintype "passive"))
      (node (ref "R11") (pin "2") (pinfunction "2_2") (pintype "passive"))
      (node (ref "R12") (pin "1") (pinfunction "1_1") (pintype "passive"))
    )
    (net (code "41") (name "Net-(U4-BST)") (class "Default")
      (node (ref "R6") (pin "2") (pinfunction "2_2") (pintype "passive"))
      (node (ref "U4") (pin "4") (pinfunction "BST_4") (pintype "passive"))
    )
    (net (code "42") (name "Net-(U4-EN{slash}SYNC)") (class "Default")
      (node (ref "R7") (pin "1") (pinfunction "1_1") (pintype "passive"))
      (node (ref "U4") (pin "3") (pinfunction "EN/SYNC_3") (pintype "passive"))
    )
    (net (code "43") (name "Net-(U4-FB)") (class "Default")
      (node (ref "R10") (pin "2") (pinfunction "2_2") (pintype "passive"))
      (node (ref "U4") (pin "1") (pinfunction "FB_1") (pintype "passive"))
    )
    (net (code "44") (name "Net-(U4-PG)") (class "Default")
      (node (ref "R9") (pin "2") (pinfunction "2_2") (pintype "passive"))
      (node (ref "U4") (pin "8") (pinfunction "PG_8") (pintype "passive"))
    )
    (net (code "45") (name "Net-(U4-SW)") (class "Default")
      (node (ref "C9") (pin "1") (pinfunction "1_1") (pintype "passive"))
      (node (ref "L2") (pin "1") (pinfunction "1_1") (pintype "passive"))
      (node (ref "U4") (pin "6") (pinfunction "SW_6") (pintype "passive"))
    )
    (net (code "46") (name "Net-(U4-VCC)") (class "Default")
      (node (ref "C16") (pin "2") (pinfunction "2_2") (pintype "passive"))
      (node (ref "R9") (pin "1") (pinfunction "1_1") (pintype "passive"))
      (node (ref "U4") (pin "2") (pinfunction "VCC_2") (pintype "passive"))
    )
    (net (code "47") (name "VIN") (class "Default")
      (node (ref "D3") (pin "1") (pinfunction "A_1") (pintype "passive"))
      (node (ref "D4") (pin "2") (pinfunction "K_2") (pintype "passive"))
      (node (ref "JP2") (pin "1") (pinfunction "1_1") (pintype "passive"))
      (node (ref "JP3") (pin "1") (pinfunction "1_1") (pintype "passive"))
    )
    (net (code "48") (name "VIN_0") (class "Default")
      (node (ref "C10") (pin "2") (pinfunction "2_2") (pintype "passive"))
      (node (ref "C11") (pin "2") (pinfunction "2_2") (pintype "passive"))
      (node (ref "C12") (pin "2") (pinfunction "2_2") (pintype "passive"))
      (node (ref "L1") (pin "2") (pinfunction "2_2") (pintype "passive"))
      (node (ref "R7") (pin "2") (pinfunction "2_2") (pintype "passive"))
      (node (ref "U4") (pin "7") (pinfunction "IN_7") (pintype "passive"))
    )
    (net (code "49") (name "unconnected-(D2-I{slash}O_2-Pad2)") (class "Default")
      (node (ref "D2") (pin "2") (pinfunction "I/O_2_2") (pintype "passive"))
    )
    (net (code "50") (name "unconnected-(D2-I{slash}O_5-Pad7)") (class "Default")
      (node (ref "D2") (pin "7") (pinfunction "I/O_5_7") (pintype "passive"))
    )
    (net (code "51") (name "unconnected-(GPS1-PPS-Pad6)") (class "Default")
      (node (ref "GPS1") (pin "6") (pinfunction "PPS_6") (pintype "passive+no_connect"))
    )
    (net (code "52") (name "unconnected-(LORA1-RXEN-Pad4)") (class "Default")
      (node (ref "LORA1") (pin "4") (pinfunction "RXEN_4") (pintype "passive"))
    )
    (net (code "53") (name "unconnected-(LORA1-TXEN-Pad2)") (class "Default")
      (node (ref "LORA1") (pin "2") (pinfunction "TXEN_2") (pintype "passive"))
    )
    (net (code "54") (name "unconnected-(U2-IO21{slash}VSPIHD{slash}EMAC_TX_EN-Pad33)") (class "Default")
      (node (ref "U2") (pin "33") (pinfunction "IO21/VSPIHD/EMAC_TX_EN_33") (pintype "passive"))
    )
    (net (code "55") (name "unconnected-(U2-IO34{slash}ADC1_CH6{slash}RTC_GPIO4-Pad6)") (class "Default")
      (node (ref "U2") (pin "6") (pinfunction "IO34/ADC1_CH6/RTC_GPIO4_6") (pintype "passive"))
    )
    (net (code "56") (name "unconnected-(U2-IO35{slash}ADC1_CH7{slash}RTC_GPIO5-Pad7)") (class "Default")
      (node (ref "U2") (pin "7") (pinfunction "IO35/ADC1_CH7/RTC_GPIO5_7") (pintype "passive"))
    )
    (net (code "57") (name "unconnected-(U2-NC_1-Pad17)") (class "Default")
      (node (ref "U2") (pin "17") (pinfunction "NC_1_17") (pintype "passive"))
    )
    (net (code "58") (name "unconnected-(U2-NC_2-Pad18)") (class "Default")
      (node (ref "U2") (pin "18") (pinfunction "NC_2_18") (pintype "passive"))
    )
    (net (code "59") (name "unconnected-(U2-NC_3-Pad19)") (class "Default")
      (node (ref "U2") (pin "19") (pinfunction "NC_3_19") (pintype "passive"))
    )
    (net (code "60") (name "unconnected-(U2-NC_4-Pad20)") (class "Default")
      (node (ref "U2") (pin "20") (pinfunction "NC_4_20") (pintype "passive"))
    )
    (net (code "61") (name "unconnected-(U2-NC_5-Pad21)") (class "Default")
      (node (ref "U2") (pin "21") (pinfunction "NC_5_21") (pintype "passive"))
    )
    (net (code "62") (name "unconnected-(U2-NC_6-Pad22)") (class "Default")
      (node (ref "U2") (pin "22") (pinfunction "NC_6_22") (pintype "passive"))
    )
    (net (code "63") (name "unconnected-(U2-NC_7-Pad32)") (class "Default")
      (node (ref "U2") (pin "32") (pinfunction "NC_7_32") (pintype "passive"))
    )
    (net (code "64") (name "unconnected-(U2-SENSOR_VN{slash}IO39{slash}ADC1_CH3{slash}RTC_GPIO3-Pad5)") (class "Default")
      (node (ref "U2") (pin "5") (pinfunction "SENSOR_VN/IO39/ADC1_CH3/RTC_GPIO3_5") (pintype "passive"))
    )
    (net (code "65") (name "unconnected-(U2-SENSOR_VP{slash}IO36{slash}ADC1_CH0{slash}RTC_GPIO0-Pad4)") (class "Default")
      (node (ref "U2") (pin "4") (pinfunction "SENSOR_VP/IO36/ADC1_CH0/RTC_GPIO0_4") (pintype "passive"))
    )
    (net (code "66") (name "unconnected-(U5-TAB-Pad2)") (class "Default")
      (node (ref "U5") (pin "2") (pinfunction "TAB_2") (pintype "passive+no_connect"))
    )
    (net (code "67") (name "unconnected-(U6-TAB-Pad2)") (class "Default")
      (node (ref "U6") (pin "2") (pinfunction "TAB_2") (pintype "passive+no_connect"))
    )
  )
)
